# PwrBrd.net
KiCad netlist of a schematic drawn in EAGLE
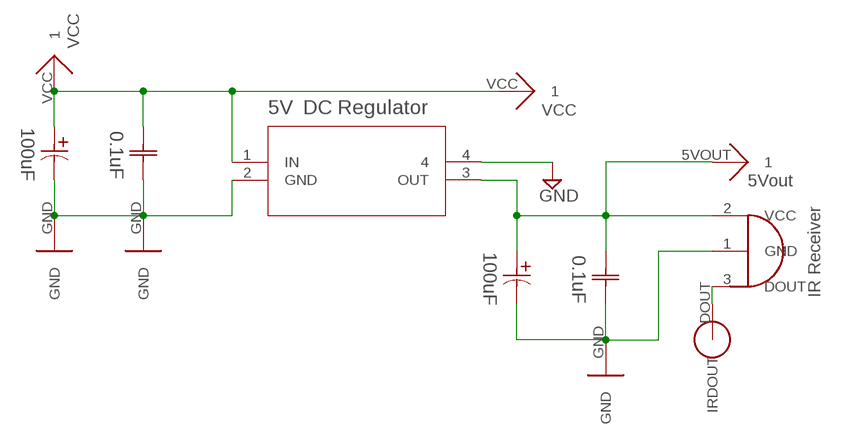
[diagram p0: schematic, sheet 1]

(export (version "E")
  (design (tool "Eeschema 10.0.6"))
  (components
    (comp (ref "C1")
      (value "UPW1A101MDD")
      (footprint "eagle-import:PCAP_5X11-THRU-ELECT")
      (libsource (lib "eagle-import") (part "UPW1A101MDD"))
    )
    (comp (ref "C2")
      (value "UPW1A101MDD")
      (footprint "eagle-import:PCAP_5X11-THRU-ELECT")
      (libsource (lib "eagle-import") (part "UPW1A101MDD"))
    )
    (comp (ref "C3")
      (value "UVR2A0R1MDD")
      (footprint "eagle-import:U1-E")
      (libsource (lib "eagle-import") (part "UVR2A0R1MDD"))
    )
    (comp (ref "C4")
      (value "UVR2A0R1MDD")
      (footprint "eagle-import:U1-E")
      (libsource (lib "eagle-import") (part "UVR2A0R1MDD"))
    )
    (comp (ref "U$1")
      (value "IRRECV")
      (footprint "eagle-import:IRRECV")
      (libsource (lib "eagle-import") (part "IRRECV"))
    )
    (comp (ref "U$2")
      (value "VCC")
      (footprint "eagle-import:VCC")
      (libsource (lib "eagle-import") (part "VCC"))
    )
    (comp (ref "U$3")
      (value "VCC")
      (footprint "eagle-import:VCC")
      (libsource (lib "eagle-import") (part "VCC"))
    )
    (comp (ref "U$4")
      (value "5VOUT")
      (footprint "eagle-import:5VOUT")
      (libsource (lib "eagle-import") (part "5VOUT"))
    )
    (comp (ref "U$5")
      (value "IRDOUT")
      (footprint "eagle-import:IRDOUT")
      (libsource (lib "eagle-import") (part "IRDOUT"))
    )
    (comp (ref "U$6")
      (value "GND")
      (footprint "eagle-import:GND")
      (libsource (lib "eagle-import") (part "GND"))
    )
    (comp (ref "U$7")
      (value "GND")
      (footprint "eagle-import:GND")
      (libsource (lib "eagle-import") (part "GND"))
    )
    (comp (ref "U$8")
      (value "GND")
      (footprint "eagle-import:GND")
      (libsource (lib "eagle-import") (part "GND"))
    )
    (comp (ref "U1")
      (value "MIC5239-5.0YS")
      (footprint "eagle-import:SOT-223_S")
      (fields (field (name "MANUFACTURER_PART_NUMBER") "MIC52395.0YS"))
      (libsource (lib "eagle-import") (part "MIC5239-5.0YS"))
    )
  )
  (nets
    (net (code "1") (name "GND") (class "Default")
      (node (ref "C1") (pin "2") (pinfunction "22_2") (pintype "passive"))
      (node (ref "C2") (pin "2") (pinfunction "22_2") (pintype "passive"))
      (node (ref "C3") (pin "2") (pinfunction "22_2") (pintype "passive"))
      (node (ref "C4") (pin "2") (pinfunction "22_2") (pintype "passive"))
      (node (ref "U$1") (pin "1") (pinfunction "GND_1") (pintype "bidirectional"))
      (node (ref "U$6") (pin "GND") (pinfunction "GND_GND") (pintype "bidirectional"))
      (node (ref "U$7") (pin "GND") (pinfunction "GND_GND") (pintype "bidirectional"))
      (node (ref "U$8") (pin "GND") (pinfunction "GND_GND") (pintype "bidirectional"))
      (node (ref "U1") (pin "2") (pinfunction "GND_2") (pintype "power_in"))
      (node (ref "U1") (pin "4") (pinfunction "4_4") (pintype "passive"))
    )
    (net (code "2") (name "Net-(C1-11)") (class "Default")
      (node (ref "C1") (pin "1") (pinfunction "11_1") (pintype "passive"))
      (node (ref "C3") (pin "1") (pinfunction "11_1") (pintype "passive"))
      (node (ref "U$2") (pin "VCC") (pinfunction "1_VCC") (pintype "bidirectional"))
      (node (ref "U$3") (pin "VCC") (pinfunction "1_VCC") (pintype "bidirectional"))
      (node (ref "U1") (pin "1") (pinfunction "IN_1") (pintype "input"))
    )
    (net (code "3") (name "Net-(C2-11)") (class "Default")
      (node (ref "C2") (pin "1") (pinfunction "11_1") (pintype "passive"))
      (node (ref "C4") (pin "1") (pinfunction "11_1") (pintype "passive"))
      (node (ref "U$1") (pin "2") (pinfunction "VCC_2") (pintype "bidirectional"))
      (node (ref "U$4") (pin "5VOUT") (pinfunction "1_5VOUT") (pintype "bidirectional"))
      (node (ref "U1") (pin "3") (pinfunction "OUT_3") (pintype "output"))
    )
    (net (code "4") (name "Net-(U$1-DOUT)") (class "Default")
      (node (ref "U$1") (pin "3") (pinfunction "DOUT_3") (pintype "bidirectional"))
      (node (ref "U$5") (pin "DOUT") (pinfunction "IRDOUT_DOUT") (pintype "bidirectional"))
    )
  )
)
